# Phase_Inverter.net
KiCad netlist of a schematic drawn in Altium Designer
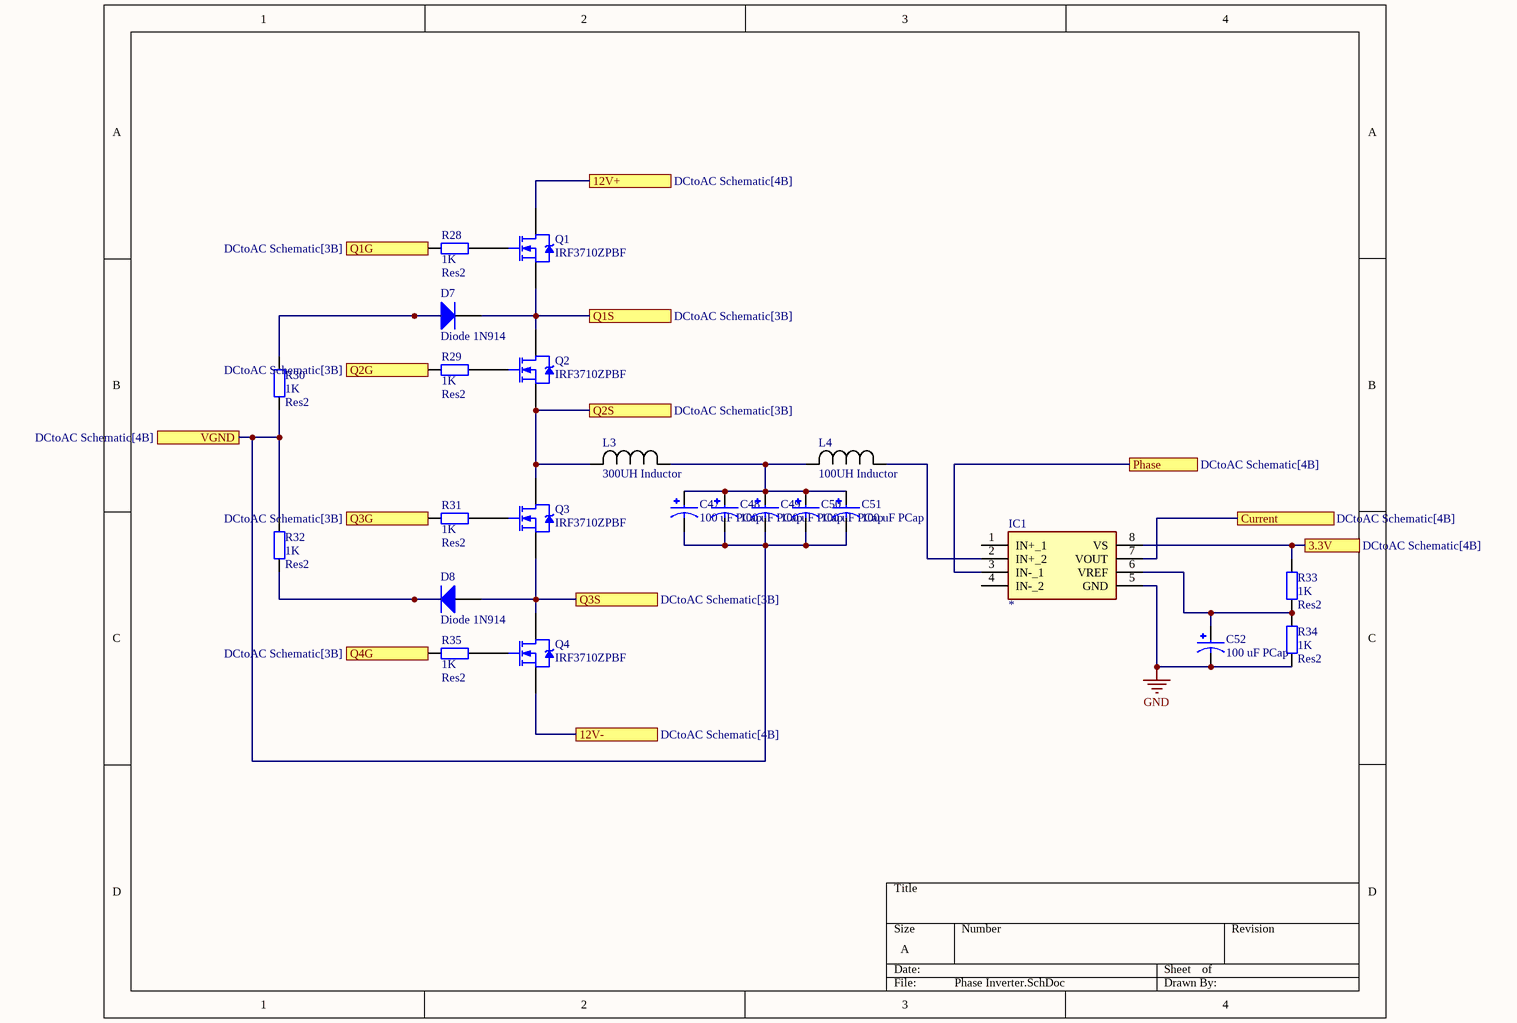
[diagram p0: Phase Inverter.SchDoc]

(export (version "E")
  (design (tool "Eeschema 10.0.6"))
  (components
    (comp (ref "C47")
      (value "100 uF PCap")
      (footprint "Senior Design PCB Library:100uF PCap")
      (description "Capacitor; Aluminum Electrolytic; Radial Al Electrolytic Cap; 100uF 63V")
      (fields (field (name "MF") "Panasonic Electronic") (field (name "MP") "EEU-FC1J101"))
      (libsource (lib "Senior Design Schematic Library") (part "100 uF PCap"))
    )
    (comp (ref "C48")
      (value "100 uF PCap")
      (footprint "Senior Design PCB Library:100uF PCap")
      (description "Capacitor; Aluminum Electrolytic; Radial Al Electrolytic Cap; 100uF 63V")
      (fields (field (name "MF") "Panasonic Electronic") (field (name "MP") "EEU-FC1J101"))
      (libsource (lib "Senior Design Schematic Library") (part "100 uF PCap"))
    )
    (comp (ref "C49")
      (value "100 uF PCap")
      (footprint "Senior Design PCB Library:100uF PCap")
      (description "Capacitor; Aluminum Electrolytic; Radial Al Electrolytic Cap; 100uF 63V")
      (fields (field (name "MF") "Panasonic Electronic") (field (name "MP") "EEU-FC1J101"))
      (libsource (lib "Senior Design Schematic Library") (part "100 uF PCap"))
    )
    (comp (ref "C50")
      (value "100 uF PCap")
      (footprint "Senior Design PCB Library:100uF PCap")
      (description "Capacitor; Aluminum Electrolytic; Radial Al Electrolytic Cap; 100uF 63V")
      (fields (field (name "MF") "Panasonic Electronic") (field (name "MP") "EEU-FC1J101"))
      (libsource (lib "Senior Design Schematic Library") (part "100 uF PCap"))
    )
    (comp (ref "C51")
      (value "100 uF PCap")
      (footprint "Senior Design PCB Library:100uF PCap")
      (description "Capacitor; Aluminum Electrolytic; Radial Al Electrolytic Cap; 100uF 63V")
      (fields (field (name "MF") "Panasonic Electronic") (field (name "MP") "EEU-FC1J101"))
      (libsource (lib "Senior Design Schematic Library") (part "100 uF PCap"))
    )
    (comp (ref "C52")
      (value "100 uF PCap")
      (footprint "Senior Design PCB Library:100uF PCap")
      (description "Capacitor; Aluminum Electrolytic; Radial Al Electrolytic Cap; 100uF 63V")
      (fields (field (name "MF") "Panasonic Electronic") (field (name "MP") "EEU-FC1J101"))
      (libsource (lib "Senior Design Schematic Library") (part "100 uF PCap"))
    )
    (comp (ref "D7")
      (value "Diode 1N914")
      (footprint "DO-35")
      (description "High Conductance Fast Diode")
      (fields (field (name "PUBLISHER") "Altium Limited"))
      (libsource (lib "Miscellaneous Devices") (part "Diode 1N914"))
    )
    (comp (ref "D8")
      (value "Diode 1N914")
      (footprint "DO-35")
      (description "High Conductance Fast Diode")
      (fields (field (name "PUBLISHER") "Altium Limited"))
      (libsource (lib "Miscellaneous Devices") (part "Diode 1N914"))
    )
    (comp (ref "IC1")
      (value "*")
      (footprint "SamacSys:SOIC127P600X175-8N")
      (description "Board Mount Current Sensors Precision isolated current sensor with external reference")
      (fields (field (name "MANUFACTURER_PART_NUMBER") "TMCS1100A2QDR"))
      (libsource (lib "*") (part "TMCS1100A2QDR"))
    )
    (comp (ref "L3")
      (value "300UH Inductor")
      (footprint "Senior Design PCB Library:1430450C_MUR")
      (libsource (lib "Senior Design Schematic Library") (part "300UH Inductor"))
    )
    (comp (ref "L4")
      (value "100UH Inductor")
      (footprint "1410460C_MUR")
      (libsource (lib "Senior Design Schematic Library") (part "100UH Inductor"))
    )
    (comp (ref "Q1")
      (value "IRF3710ZPBF")
      (footprint "Senior Design PCB Library:PG-TO220-3_INF")
      (description "N-Channel Power MOSFET")
      (fields (field (name "PUBLISHER") "Altium Limited"))
      (libsource (lib "Senior Design Schematic Library") (part "IRF3710ZPBF"))
    )
    (comp (ref "Q2")
      (value "IRF3710ZPBF")
      (footprint "Senior Design PCB Library:PG-TO220-3_INF")
      (description "N-Channel Power MOSFET")
      (fields (field (name "PUBLISHER") "Altium Limited"))
      (libsource (lib "Senior Design Schematic Library") (part "IRF3710ZPBF"))
    )
    (comp (ref "Q3")
      (value "IRF3710ZPBF")
      (footprint "Senior Design PCB Library:PG-TO220-3_INF")
      (description "N-Channel Power MOSFET")
      (fields (field (name "PUBLISHER") "Altium Limited"))
      (libsource (lib "Senior Design Schematic Library") (part "IRF3710ZPBF"))
    )
    (comp (ref "Q4")
      (value "IRF3710ZPBF")
      (footprint "Senior Design PCB Library:PG-TO220-3_INF")
      (description "N-Channel Power MOSFET")
      (fields (field (name "PUBLISHER") "Altium Limited"))
      (libsource (lib "Senior Design Schematic Library") (part "IRF3710ZPBF"))
    )
    (comp (ref "R28")
      (value "Res2")
      (footprint "AXIAL-0.4")
      (description "Resistor")
      (fields (field (name "ALTIUM_VALUE") "1K") (field (name "PUBLISHER") "Altium Limited"))
      (libsource (lib "") (part "Res2_2"))
    )
    (comp (ref "R29")
      (value "Res2")
      (footprint "AXIAL-0.4")
      (description "Resistor")
      (fields (field (name "ALTIUM_VALUE") "1K") (field (name "PUBLISHER") "Altium Limited"))
      (libsource (lib "") (part "Res2_2"))
    )
    (comp (ref "R30")
      (value "Res2")
      (footprint "AXIAL-0.4")
      (description "Resistor")
      (fields (field (name "ALTIUM_VALUE") "1K") (field (name "PUBLISHER") "Altium Limited"))
      (libsource (lib "Miscellaneous Devices") (part "Res2"))
    )
    (comp (ref "R31")
      (value "Res2")
      (footprint "AXIAL-0.4")
      (description "Resistor")
      (fields (field (name "ALTIUM_VALUE") "1K") (field (name "PUBLISHER") "Altium Limited"))
      (libsource (lib "") (part "Res2_2"))
    )
    (comp (ref "R32")
      (value "Res2")
      (footprint "AXIAL-0.4")
      (description "Resistor")
      (fields (field (name "ALTIUM_VALUE") "1K") (field (name "PUBLISHER") "Altium Limited"))
      (libsource (lib "Miscellaneous Devices") (part "Res2"))
    )
    (comp (ref "R33")
      (value "Res2")
      (footprint "AXIAL-0.4")
      (description "Resistor")
      (fields (field (name "ALTIUM_VALUE") "1K") (field (name "PUBLISHER") "Altium Limited"))
      (libsource (lib "") (part "Res2_1"))
    )
    (comp (ref "R34")
      (value "Res2")
      (footprint "AXIAL-0.4")
      (description "Resistor")
      (fields (field (name "ALTIUM_VALUE") "1K") (field (name "PUBLISHER") "Altium Limited"))
      (libsource (lib "") (part "Res2_1"))
    )
    (comp (ref "R35")
      (value "Res2")
      (footprint "AXIAL-0.4")
      (description "Resistor")
      (fields (field (name "ALTIUM_VALUE") "1K") (field (name "PUBLISHER") "Altium Limited"))
      (libsource (lib "") (part "Res2_2"))
    )
  )
  (nets
    (net (code "1") (name "/3.3V") (class "Default")
      (node (ref "IC1") (pin "8") (pinfunction "VS_8") (pintype "passive"))
      (node (ref "R33") (pin "1") (pinfunction "1_1") (pintype "passive"))
    )
    (net (code "2") (name "/12V+") (class "Default")
      (node (ref "Q1") (pin "2") (pinfunction "D_2") (pintype "passive"))
    )
    (net (code "3") (name "/12V-") (class "Default")
      (node (ref "Q4") (pin "3") (pinfunction "S_3") (pintype "passive"))
    )
    (net (code "4") (name "/Current") (class "Default")
      (node (ref "IC1") (pin "7") (pinfunction "VOUT_7") (pintype "passive"))
    )
    (net (code "5") (name "/Phase") (class "Default")
      (node (ref "IC1") (pin "3") (pinfunction "IN-_1_3") (pintype "passive"))
    )
    (net (code "6") (name "/Q1G") (class "Default")
      (node (ref "R28") (pin "1") (pinfunction "1_1") (pintype "passive"))
    )
    (net (code "7") (name "/Q1S") (class "Default")
      (node (ref "D7") (pin "2") (pinfunction "K_2") (pintype "passive"))
      (node (ref "Q1") (pin "3") (pinfunction "S_3") (pintype "passive"))
      (node (ref "Q2") (pin "2") (pinfunction "D_2") (pintype "passive"))
    )
    (net (code "8") (name "/Q2G") (class "Default")
      (node (ref "R29") (pin "1") (pinfunction "1_1") (pintype "passive"))
    )
    (net (code "9") (name "/Q2S") (class "Default")
      (node (ref "L3") (pin "2") (pinfunction "2_2") (pintype "passive"))
      (node (ref "Q2") (pin "3") (pinfunction "S_3") (pintype "passive"))
      (node (ref "Q3") (pin "2") (pinfunction "D_2") (pintype "passive"))
    )
    (net (code "10") (name "/Q3G") (class "Default")
      (node (ref "R31") (pin "1") (pinfunction "1_1") (pintype "passive"))
    )
    (net (code "11") (name "/Q3S") (class "Default")
      (node (ref "D8") (pin "1") (pinfunction "A_1") (pintype "passive"))
      (node (ref "Q3") (pin "3") (pinfunction "S_3") (pintype "passive"))
      (node (ref "Q4") (pin "2") (pinfunction "D_2") (pintype "passive"))
    )
    (net (code "12") (name "/Q4G") (class "Default")
      (node (ref "R35") (pin "1") (pinfunction "1_1") (pintype "passive"))
    )
    (net (code "13") (name "/VGND") (class "Default")
      (node (ref "C47") (pin "N") (pinfunction "N_N") (pintype "passive"))
      (node (ref "C48") (pin "N") (pinfunction "N_N") (pintype "passive"))
      (node (ref "C49") (pin "N") (pinfunction "N_N") (pintype "passive"))
      (node (ref "C50") (pin "N") (pinfunction "N_N") (pintype "passive"))
      (node (ref "C51") (pin "N") (pinfunction "N_N") (pintype "passive"))
      (node (ref "R30") (pin "1") (pinfunction "1_1") (pintype "passive"))
      (node (ref "R32") (pin "2") (pinfunction "2_2") (pintype "passive"))
    )
    (net (code "14") (name "GND") (class "Default")
      (node (ref "C52") (pin "N") (pinfunction "N_N") (pintype "passive"))
      (node (ref "IC1") (pin "5") (pinfunction "GND_5") (pintype "passive"))
      (node (ref "R34") (pin "2") (pinfunction "2_2") (pintype "passive"))
    )
    (net (code "15") (name "Net-(C47-PadP)") (class "Default")
      (node (ref "C47") (pin "P") (pinfunction "P_P") (pintype "passive"))
      (node (ref "C48") (pin "P") (pinfunction "P_P") (pintype "passive"))
      (node (ref "C49") (pin "P") (pinfunction "P_P") (pintype "passive"))
      (node (ref "C50") (pin "P") (pinfunction "P_P") (pintype "passive"))
      (node (ref "C51") (pin "P") (pinfunction "P_P") (pintype "passive"))
      (node (ref "L3") (pin "1") (pinfunction "1_1") (pintype "passive"))
      (node (ref "L4") (pin "2") (pinfunction "2_2") (pintype "passive"))
    )
    (net (code "16") (name "Net-(D7-A)") (class "Default")
      (node (ref "D7") (pin "1") (pinfunction "A_1") (pintype "passive"))
      (node (ref "R30") (pin "2") (pinfunction "2_2") (pintype "passive"))
    )
    (net (code "17") (name "Net-(D8-K)") (class "Default")
      (node (ref "D8") (pin "2") (pinfunction "K_2") (pintype "passive"))
      (node (ref "R32") (pin "1") (pinfunction "1_1") (pintype "passive"))
    )
    (net (code "18") (name "Net-(IC1-IN+_2)") (class "Default")
      (node (ref "IC1") (pin "2") (pinfunction "IN+_2_2") (pintype "passive"))
      (node (ref "L4") (pin "1") (pinfunction "1_1") (pintype "passive"))
    )
    (net (code "19") (name "Net-(IC1-VREF)") (class "Default")
      (node (ref "C52") (pin "P") (pinfunction "P_P") (pintype "passive"))
      (node (ref "IC1") (pin "6") (pinfunction "VREF_6") (pintype "passive"))
      (node (ref "R33") (pin "2") (pinfunction "2_2") (pintype "passive"))
      (node (ref "R34") (pin "1") (pinfunction "1_1") (pintype "passive"))
    )
    (net (code "20") (name "Net-(Q1-G)") (class "Default")
      (node (ref "Q1") (pin "1") (pinfunction "G_1") (pintype "passive"))
      (node (ref "R28") (pin "2") (pinfunction "2_2") (pintype "passive"))
    )
    (net (code "21") (name "Net-(Q2-G)") (class "Default")
      (node (ref "Q2") (pin "1") (pinfunction "G_1") (pintype "passive"))
      (node (ref "R29") (pin "2") (pinfunction "2_2") (pintype "passive"))
    )
    (net (code "22") (name "Net-(Q3-G)") (class "Default")
      (node (ref "Q3") (pin "1") (pinfunction "G_1") (pintype "passive"))
      (node (ref "R31") (pin "2") (pinfunction "2_2") (pintype "passive"))
    )
    (net (code "23") (name "Net-(Q4-G)") (class "Default")
      (node (ref "Q4") (pin "1") (pinfunction "G_1") (pintype "passive"))
      (node (ref "R35") (pin "2") (pinfunction "2_2") (pintype "passive"))
    )
    (net (code "24") (name "unconnected-(IC1-IN+_1-Pad1)") (class "Default")
      (node (ref "IC1") (pin "1") (pinfunction "IN+_1_1") (pintype "passive"))
    )
    (net (code "25") (name "unconnected-(IC1-IN-_2-Pad4)") (class "Default")
      (node (ref "IC1") (pin "4") (pinfunction "IN-_2_4") (pintype "passive"))
    )
  )
)
